# ts-w5500.net
KiCad netlist of a schematic drawn in EAGLE
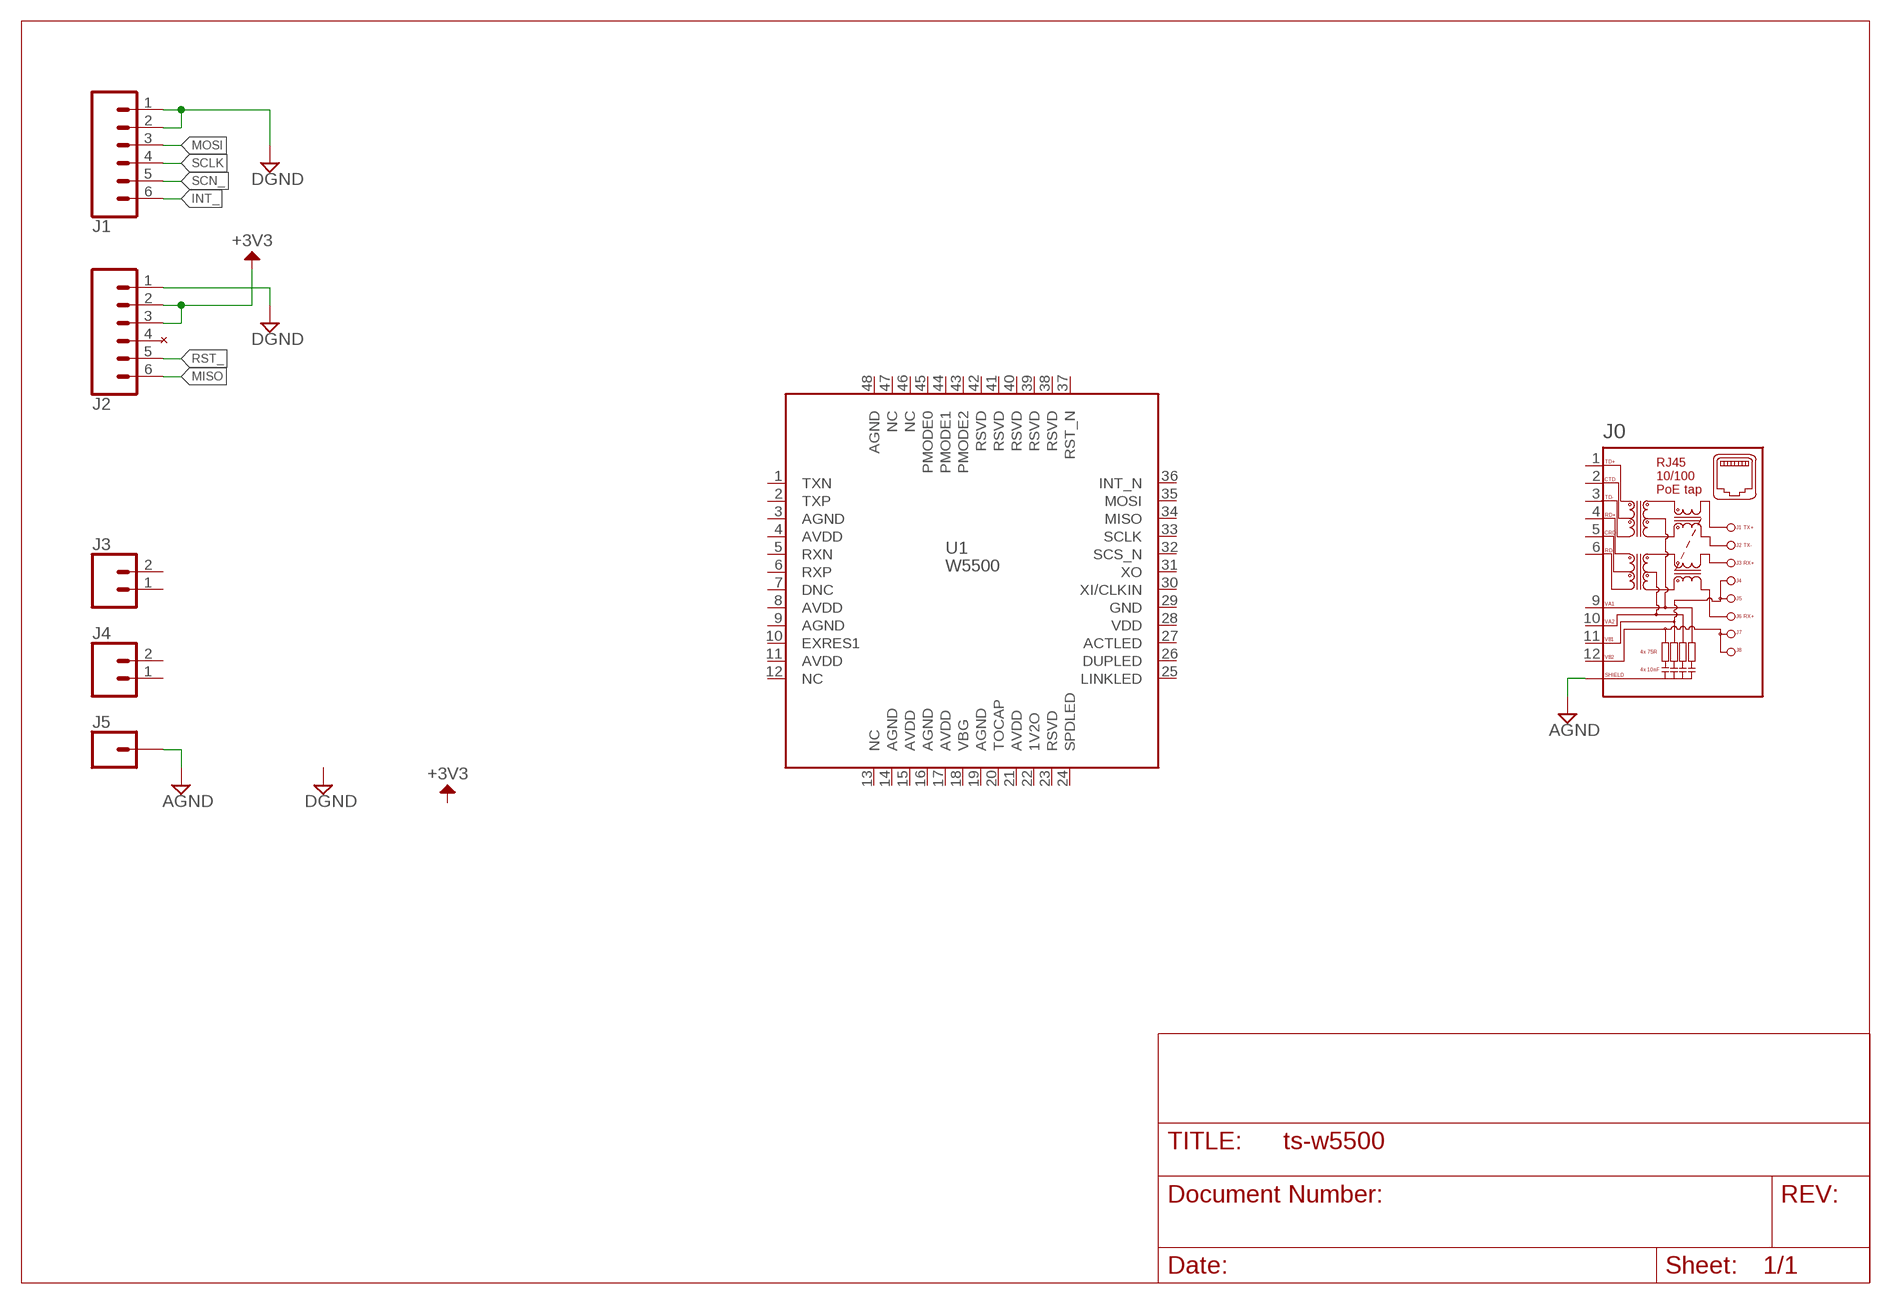
[diagram p0: schematic, sheet 1]

(export (version "E")
  (design (tool "Eeschema 10.0.6"))
  (components
    (comp (ref "J0")
      (value "7498210003")
      (footprint "eagle-import:SMD_7498210003")
      (libsource (lib "eagle-import") (part "7498210003"))
    )
    (comp (ref "J1")
      (value "CONN_06NO_SILK_NO_POP")
      (footprint "eagle-import:1X06_NO_SILK")
      (libsource (lib "eagle-import") (part "CONN_06NO_SILK_NO_POP"))
    )
    (comp (ref "J2")
      (value "CONN_06NO_SILK_NO_POP")
      (footprint "eagle-import:1X06_NO_SILK")
      (libsource (lib "eagle-import") (part "CONN_06NO_SILK_NO_POP"))
    )
    (comp (ref "J3")
      (value "CONN_021X02_NO_SILK")
      (footprint "eagle-import:1X02_NO_SILK")
      (libsource (lib "eagle-import") (part "CONN_021X02_NO_SILK"))
    )
    (comp (ref "J4")
      (value "CONN_021X02_NO_SILK")
      (footprint "eagle-import:1X02_NO_SILK")
      (libsource (lib "eagle-import") (part "CONN_021X02_NO_SILK"))
    )
    (comp (ref "J5")
      (value "CONN_01")
      (footprint "eagle-import:1X01")
      (libsource (lib "eagle-import") (part "CONN_01"))
    )
    (comp (ref "U1")
      (value "W5500")
      (footprint "eagle-import:W5500")
      (libsource (lib "eagle-import") (part "W5500"))
    )
  )
  (nets
    (net (code "1") (name "+3V3") (class "Default")
      (node (ref "J2") (pin "2") (pinfunction "2_2") (pintype "passive"))
      (node (ref "J2") (pin "3") (pinfunction "3_3") (pintype "passive"))
    )
    (net (code "2") (name "AGND") (class "Default")
      (node (ref "J0") (pin "13") (pinfunction "SHIELD_13") (pintype "passive"))
      (node (ref "J0") (pin "14") (pinfunction "SHIELD_14") (pintype "passive"))
      (node (ref "J5") (pin "1") (pinfunction "1_1") (pintype "passive"))
    )
    (net (code "3") (name "DGND") (class "Default")
      (node (ref "J1") (pin "1") (pinfunction "1_1") (pintype "passive"))
      (node (ref "J1") (pin "2") (pinfunction "2_2") (pintype "passive"))
      (node (ref "J2") (pin "1") (pinfunction "1_1") (pintype "passive"))
    )
    (net (code "4") (name "INT_") (class "Default")
      (node (ref "J1") (pin "6") (pinfunction "6_6") (pintype "passive"))
    )
    (net (code "5") (name "MISO") (class "Default")
      (node (ref "J2") (pin "6") (pinfunction "6_6") (pintype "passive"))
    )
    (net (code "6") (name "MOSI") (class "Default")
      (node (ref "J1") (pin "3") (pinfunction "3_3") (pintype "passive"))
    )
    (net (code "7") (name "RST_") (class "Default")
      (node (ref "J2") (pin "5") (pinfunction "5_5") (pintype "passive"))
    )
    (net (code "8") (name "SCLK") (class "Default")
      (node (ref "J1") (pin "4") (pinfunction "4_4") (pintype "passive"))
    )
    (net (code "9") (name "SCN_") (class "Default")
      (node (ref "J1") (pin "5") (pinfunction "5_5") (pintype "passive"))
    )
    (net (code "10") (name "unconnected-(J0-Pad1)") (class "Default")
      (node (ref "J0") (pin "1") (pinfunction "1_1") (pintype "passive"))
    )
    (net (code "11") (name "unconnected-(J0-Pad2)") (class "Default")
      (node (ref "J0") (pin "2") (pinfunction "2_2") (pintype "passive"))
    )
    (net (code "12") (name "unconnected-(J0-Pad3)") (class "Default")
      (node (ref "J0") (pin "3") (pinfunction "3_3") (pintype "passive"))
    )
    (net (code "13") (name "unconnected-(J0-Pad4)") (class "Default")
      (node (ref "J0") (pin "4") (pinfunction "4_4") (pintype "passive"))
    )
    (net (code "14") (name "unconnected-(J0-Pad5)") (class "Default")
      (node (ref "J0") (pin "5") (pinfunction "5_5") (pintype "passive"))
    )
    (net (code "15") (name "unconnected-(J0-Pad6)") (class "Default")
      (node (ref "J0") (pin "6") (pinfunction "6_6") (pintype "passive"))
    )
    (net (code "16") (name "unconnected-(J0-Pad9)") (class "Default")
      (node (ref "J0") (pin "9") (pinfunction "9_9") (pintype "passive"))
    )
    (net (code "17") (name "unconnected-(J0-Pad10)") (class "Default")
      (node (ref "J0") (pin "10") (pinfunction "10_10") (pintype "passive"))
    )
    (net (code "18") (name "unconnected-(J0-Pad11)") (class "Default")
      (node (ref "J0") (pin "11") (pinfunction "11_11") (pintype "passive"))
    )
    (net (code "19") (name "unconnected-(J0-Pad12)") (class "Default")
      (node (ref "J0") (pin "12") (pinfunction "12_12") (pintype "passive"))
    )
    (net (code "20") (name "unconnected-(J2-Pad4)") (class "Default")
      (node (ref "J2") (pin "4") (pinfunction "4_4") (pintype "passive"))
    )
    (net (code "21") (name "unconnected-(J3-Pad1)") (class "Default")
      (node (ref "J3") (pin "1") (pinfunction "1_1") (pintype "passive"))
    )
    (net (code "22") (name "unconnected-(J3-Pad2)") (class "Default")
      (node (ref "J3") (pin "2") (pinfunction "2_2") (pintype "passive"))
    )
    (net (code "23") (name "unconnected-(J4-Pad1)") (class "Default")
      (node (ref "J4") (pin "1") (pinfunction "1_1") (pintype "passive"))
    )
    (net (code "24") (name "unconnected-(J4-Pad2)") (class "Default")
      (node (ref "J4") (pin "2") (pinfunction "2_2") (pintype "passive"))
    )
    (net (code "25") (name "unconnected-(U1-1V2O-Pad22)") (class "Default")
      (node (ref "U1") (pin "22") (pinfunction "1V2O_22") (pintype "passive"))
    )
    (net (code "26") (name "unconnected-(U1-ACTLED-Pad27)") (class "Default")
      (node (ref "U1") (pin "27") (pinfunction "ACTLED_27") (pintype "passive"))
    )
    (net (code "27") (name "unconnected-(U1-AGND-Pad3)") (class "Default")
      (node (ref "U1") (pin "3") (pinfunction "AGND_3") (pintype "passive"))
    )
    (net (code "28") (name "unconnected-(U1-AGND-Pad9)") (class "Default")
      (node (ref "U1") (pin "9") (pinfunction "AGND_9") (pintype "passive"))
    )
    (net (code "29") (name "unconnected-(U1-AGND-Pad14)") (class "Default")
      (node (ref "U1") (pin "14") (pinfunction "AGND_14") (pintype "passive"))
    )
    (net (code "30") (name "unconnected-(U1-AGND-Pad16)") (class "Default")
      (node (ref "U1") (pin "16") (pinfunction "AGND_16") (pintype "passive"))
    )
    (net (code "31") (name "unconnected-(U1-AGND-Pad19)") (class "Default")
      (node (ref "U1") (pin "19") (pinfunction "AGND_19") (pintype "passive"))
    )
    (net (code "32") (name "unconnected-(U1-AGND-Pad48)") (class "Default")
      (node (ref "U1") (pin "48") (pinfunction "AGND_48") (pintype "passive"))
    )
    (net (code "33") (name "unconnected-(U1-AVDD-Pad4)") (class "Default")
      (node (ref "U1") (pin "4") (pinfunction "AVDD_4") (pintype "passive"))
    )
    (net (code "34") (name "unconnected-(U1-AVDD-Pad8)") (class "Default")
      (node (ref "U1") (pin "8") (pinfunction "AVDD_8") (pintype "passive"))
    )
    (net (code "35") (name "unconnected-(U1-AVDD-Pad11)") (class "Default")
      (node (ref "U1") (pin "11") (pinfunction "AVDD_11") (pintype "passive"))
    )
    (net (code "36") (name "unconnected-(U1-AVDD-Pad15)") (class "Default")
      (node (ref "U1") (pin "15") (pinfunction "AVDD_15") (pintype "passive"))
    )
    (net (code "37") (name "unconnected-(U1-AVDD-Pad17)") (class "Default")
      (node (ref "U1") (pin "17") (pinfunction "AVDD_17") (pintype "passive"))
    )
    (net (code "38") (name "unconnected-(U1-AVDD-Pad21)") (class "Default")
      (node (ref "U1") (pin "21") (pinfunction "AVDD_21") (pintype "passive"))
    )
    (net (code "39") (name "unconnected-(U1-DNC-Pad7)") (class "Default")
      (node (ref "U1") (pin "7") (pinfunction "DNC_7") (pintype "passive"))
    )
    (net (code "40") (name "unconnected-(U1-DUPLED-Pad26)") (class "Default")
      (node (ref "U1") (pin "26") (pinfunction "DUPLED_26") (pintype "passive"))
    )
    (net (code "41") (name "unconnected-(U1-EXRES1-Pad10)") (class "Default")
      (node (ref "U1") (pin "10") (pinfunction "EXRES1_10") (pintype "passive"))
    )
    (net (code "42") (name "unconnected-(U1-GND-Pad29)") (class "Default")
      (node (ref "U1") (pin "29") (pinfunction "GND_29") (pintype "passive"))
    )
    (net (code "43") (name "unconnected-(U1-INT_N-Pad36)") (class "Default")
      (node (ref "U1") (pin "36") (pinfunction "INT_N_36") (pintype "passive"))
    )
    (net (code "44") (name "unconnected-(U1-LINKLED-Pad25)") (class "Default")
      (node (ref "U1") (pin "25") (pinfunction "LINKLED_25") (pintype "passive"))
    )
    (net (code "45") (name "unconnected-(U1-MISO-Pad34)") (class "Default")
      (node (ref "U1") (pin "34") (pinfunction "MISO_34") (pintype "passive"))
    )
    (net (code "46") (name "unconnected-(U1-MOSI-Pad35)") (class "Default")
      (node (ref "U1") (pin "35") (pinfunction "MOSI_35") (pintype "passive"))
    )
    (net (code "47") (name "unconnected-(U1-NC-Pad12)") (class "Default")
      (node (ref "U1") (pin "12") (pinfunction "NC_12") (pintype "passive"))
    )
    (net (code "48") (name "unconnected-(U1-NC-Pad13)") (class "Default")
      (node (ref "U1") (pin "13") (pinfunction "NC_13") (pintype "passive"))
    )
    (net (code "49") (name "unconnected-(U1-NC-Pad46)") (class "Default")
      (node (ref "U1") (pin "46") (pinfunction "NC_46") (pintype "passive"))
    )
    (net (code "50") (name "unconnected-(U1-NC-Pad47)") (class "Default")
      (node (ref "U1") (pin "47") (pinfunction "NC_47") (pintype "passive"))
    )
    (net (code "51") (name "unconnected-(U1-PMODE0-Pad45)") (class "Default")
      (node (ref "U1") (pin "45") (pinfunction "PMODE0_45") (pintype "passive"))
    )
    (net (code "52") (name "unconnected-(U1-PMODE1-Pad44)") (class "Default")
      (node (ref "U1") (pin "44") (pinfunction "PMODE1_44") (pintype "passive"))
    )
    (net (code "53") (name "unconnected-(U1-PMODE2-Pad43)") (class "Default")
      (node (ref "U1") (pin "43") (pinfunction "PMODE2_43") (pintype "passive"))
    )
    (net (code "54") (name "unconnected-(U1-RST_N-Pad37)") (class "Default")
      (node (ref "U1") (pin "37") (pinfunction "RST_N_37") (pintype "passive"))
    )
    (net (code "55") (name "unconnected-(U1-RSVD-Pad23)") (class "Default")
      (node (ref "U1") (pin "23") (pinfunction "RSVD_23") (pintype "passive"))
    )
    (net (code "56") (name "unconnected-(U1-RSVD-Pad38)") (class "Default")
      (node (ref "U1") (pin "38") (pinfunction "RSVD_38") (pintype "passive"))
    )
    (net (code "57") (name "unconnected-(U1-RSVD-Pad39)") (class "Default")
      (node (ref "U1") (pin "39") (pinfunction "RSVD_39") (pintype "passive"))
    )
    (net (code "58") (name "unconnected-(U1-RSVD-Pad40)") (class "Default")
      (node (ref "U1") (pin "40") (pinfunction "RSVD_40") (pintype "passive"))
    )
    (net (code "59") (name "unconnected-(U1-RSVD-Pad41)") (class "Default")
      (node (ref "U1") (pin "41") (pinfunction "RSVD_41") (pintype "passive"))
    )
    (net (code "60") (name "unconnected-(U1-RSVD-Pad42)") (class "Default")
      (node (ref "U1") (pin "42") (pinfunction "RSVD_42") (pintype "passive"))
    )
    (net (code "61") (name "unconnected-(U1-RXN-Pad5)") (class "Default")
      (node (ref "U1") (pin "5") (pinfunction "RXN_5") (pintype "passive"))
    )
    (net (code "62") (name "unconnected-(U1-RXP-Pad6)") (class "Default")
      (node (ref "U1") (pin "6") (pinfunction "RXP_6") (pintype "passive"))
    )
    (net (code "63") (name "unconnected-(U1-SCLK-Pad33)") (class "Default")
      (node (ref "U1") (pin "33") (pinfunction "SCLK_33") (pintype "passive"))
    )
    (net (code "64") (name "unconnected-(U1-SCS_N-Pad32)") (class "Default")
      (node (ref "U1") (pin "32") (pinfunction "SCS_N_32") (pintype "passive"))
    )
    (net (code "65") (name "unconnected-(U1-SPDLED-Pad24)") (class "Default")
      (node (ref "U1") (pin "24") (pinfunction "SPDLED_24") (pintype "passive"))
    )
    (net (code "66") (name "unconnected-(U1-TOCAP-Pad20)") (class "Default")
      (node (ref "U1") (pin "20") (pinfunction "TOCAP_20") (pintype "passive"))
    )
    (net (code "67") (name "unconnected-(U1-TXN-Pad1)") (class "Default")
      (node (ref "U1") (pin "1") (pinfunction "TXN_1") (pintype "passive"))
    )
    (net (code "68") (name "unconnected-(U1-TXP-Pad2)") (class "Default")
      (node (ref "U1") (pin "2") (pinfunction "TXP_2") (pintype "passive"))
    )
    (net (code "69") (name "unconnected-(U1-VBG-Pad18)") (class "Default")
      (node (ref "U1") (pin "18") (pinfunction "VBG_18") (pintype "passive"))
    )
    (net (code "70") (name "unconnected-(U1-VDD-Pad28)") (class "Default")
      (node (ref "U1") (pin "28") (pinfunction "VDD_28") (pintype "passive"))
    )
    (net (code "71") (name "unconnected-(U1-XI{slash}CLKIN-Pad30)") (class "Default")
      (node (ref "U1") (pin "30") (pinfunction "XI/CLKIN_30") (pintype "passive"))
    )
    (net (code "72") (name "unconnected-(U1-XO-Pad31)") (class "Default")
      (node (ref "U1") (pin "31") (pinfunction "XO_31") (pintype "passive"))
    )
  )
)
